# Amogus.net
KiCad netlist of a schematic drawn in EasyEDA
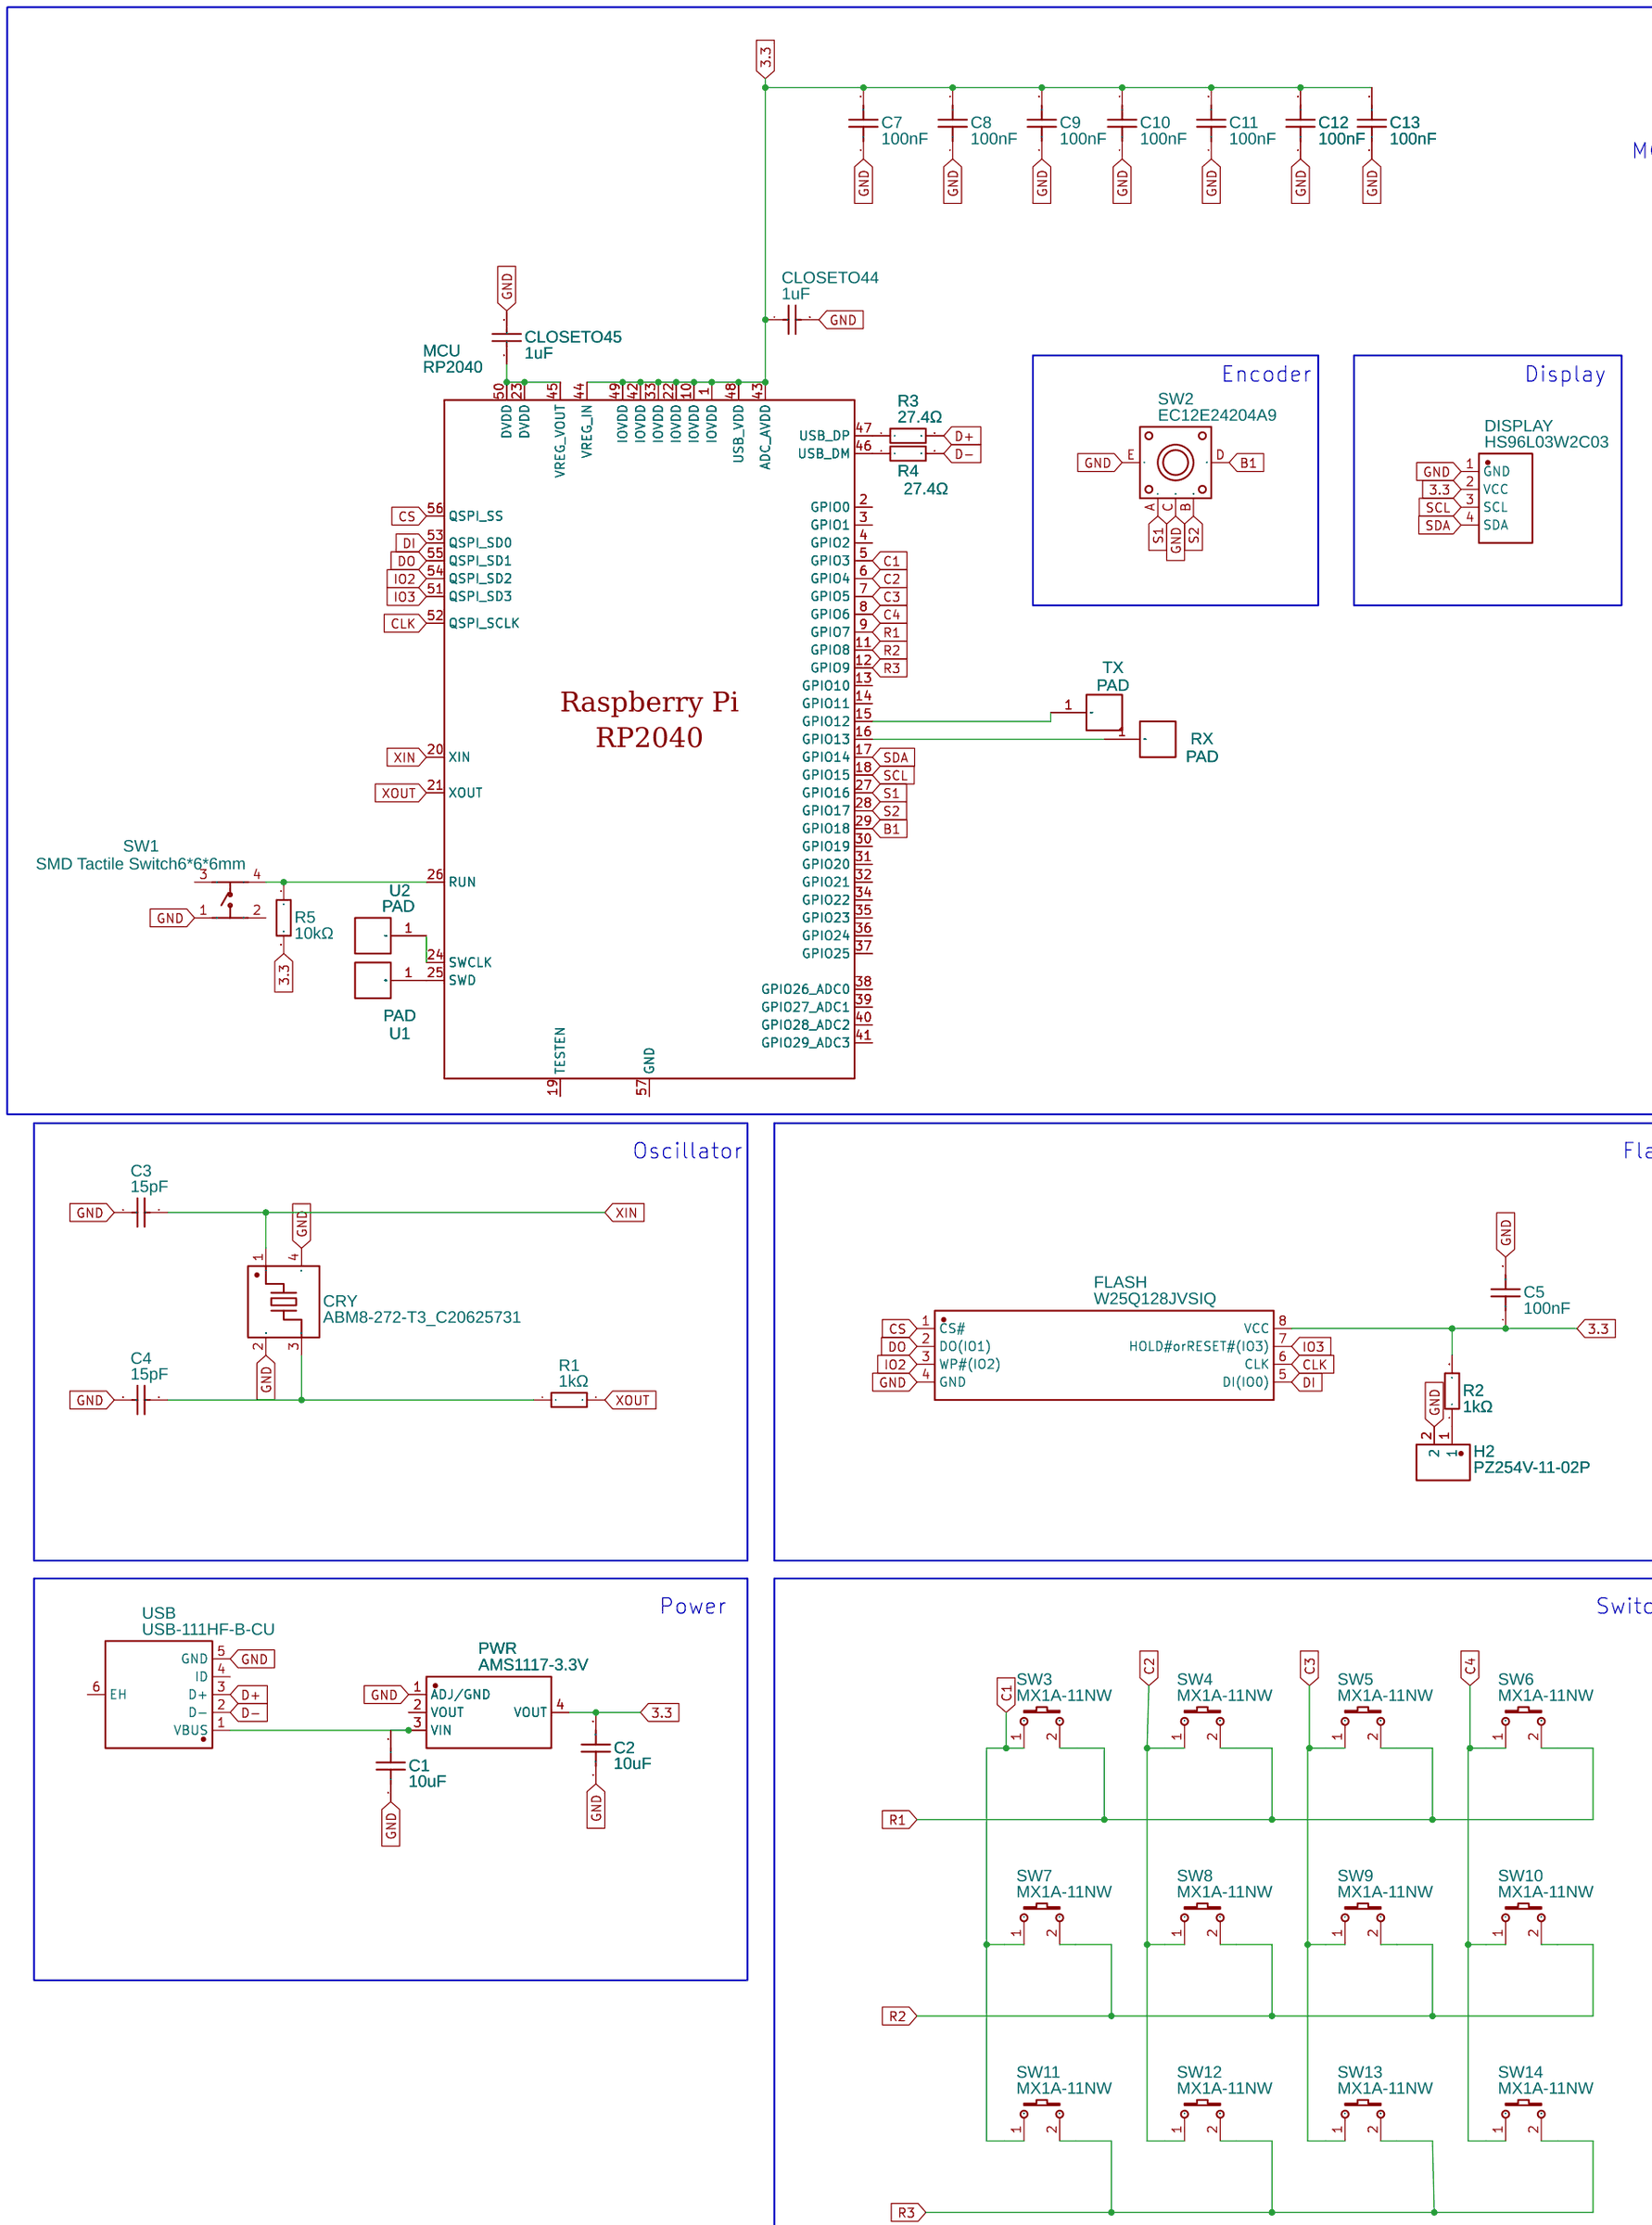
[diagram p0: schematic sheet]

(export (version "E")
  (design (tool "Eeschema 10.0.6"))
  (components
    (comp (ref "C1")
      (value "10uF")
      (fields
        (field (name "Manufacturer Part") "CL21A106KAYNNNE")
        (field (name "Manufacturer") "SAMSUNG(三星)")
      )
      (libsource (lib "") (part "CL21A106KAYNNNE"))
    )
    (comp (ref "C2")
      (value "10uF")
      (fields
        (field (name "Manufacturer Part") "CL21A106KAYNNNE")
        (field (name "Manufacturer") "SAMSUNG(三星)")
      )
      (libsource (lib "") (part "CL21A106KAYNNNE"))
    )
    (comp (ref "C3")
      (value "15pF")
      (fields (field (name "Manufacturer Part") "0805CG150J500NT") (field (name "Manufacturer") "FH(风华)"))
      (libsource (lib "") (part "0805CG150J500NT"))
    )
    (comp (ref "C4")
      (value "15pF")
      (fields (field (name "Manufacturer Part") "0805CG150J500NT") (field (name "Manufacturer") "FH(风华)"))
      (libsource (lib "") (part "0805CG150J500NT"))
    )
    (comp (ref "C5")
      (value "100nF")
      (fields
        (field (name "Manufacturer Part") "CC0603KRX7R9BB104")
        (field (name "Manufacturer") "YAGEO(国巨)")
      )
      (libsource (lib "") (part "CC0603KRX7R9BB104"))
    )
    (comp (ref "C7")
      (value "100nF")
      (fields
        (field (name "Manufacturer Part") "CC0603KRX7R9BB104")
        (field (name "Manufacturer") "YAGEO(国巨)")
      )
      (libsource (lib "") (part "CC0603KRX7R9BB104"))
    )
    (comp (ref "C8")
      (value "100nF")
      (fields
        (field (name "Manufacturer Part") "CC0603KRX7R9BB104")
        (field (name "Manufacturer") "YAGEO(国巨)")
      )
      (libsource (lib "") (part "CC0603KRX7R9BB104"))
    )
    (comp (ref "C9")
      (value "100nF")
      (fields
        (field (name "Manufacturer Part") "CC0603KRX7R9BB104")
        (field (name "Manufacturer") "YAGEO(国巨)")
      )
      (libsource (lib "") (part "CC0603KRX7R9BB104"))
    )
    (comp (ref "C10")
      (value "100nF")
      (fields
        (field (name "Manufacturer Part") "CC0603KRX7R9BB104")
        (field (name "Manufacturer") "YAGEO(国巨)")
      )
      (libsource (lib "") (part "CC0603KRX7R9BB104"))
    )
    (comp (ref "C11")
      (value "100nF")
      (fields
        (field (name "Manufacturer Part") "CC0603KRX7R9BB104")
        (field (name "Manufacturer") "YAGEO(国巨)")
      )
      (libsource (lib "") (part "CC0603KRX7R9BB104"))
    )
    (comp (ref "C12")
      (value "100nF")
      (fields
        (field (name "Manufacturer Part") "CC0603KRX7R9BB104")
        (field (name "Manufacturer") "YAGEO(国巨)")
      )
      (libsource (lib "") (part "CC0603KRX7R9BB104"))
    )
    (comp (ref "C13")
      (value "100nF")
      (fields
        (field (name "Manufacturer Part") "CC0603KRX7R9BB104")
        (field (name "Manufacturer") "YAGEO(国巨)")
      )
      (libsource (lib "") (part "CC0603KRX7R9BB104"))
    )
    (comp (ref "CLOSETO44")
      (value "1uF")
      (fields
        (field (name "Manufacturer Part") "GRM155R61E105KA12D")
        (field (name "Manufacturer") "muRata(村田)")
      )
      (libsource (lib "") (part "GRM155R61E105KA12D_1"))
    )
    (comp (ref "CLOSETO45")
      (value "1uF")
      (fields
        (field (name "Manufacturer Part") "GRM155R61E105KA12D")
        (field (name "Manufacturer") "muRata(村田)")
      )
      (libsource (lib "") (part "GRM155R61E105KA12D"))
    )
    (comp (ref "CRY")
      (value "ABM8-272-T3_C20625731")
      (fields (field (name "Manufacturer Part") "ABM8-272-T3") (field (name "Manufacturer") "ABRACON"))
      (libsource (lib "") (part "ABM8-272-T3_C20625731"))
    )
    (comp (ref "DISPLAY")
      (value "HS96L03W2C03")
      (fields (field (name "Manufacturer") "HS(汉昇)"))
      (libsource (lib "") (part "HS96L03W2C03"))
    )
    (comp (ref "FLASH")
      (value "W25Q128JVSIQ")
      (fields (field (name "Manufacturer") "WINBOND(华邦)"))
      (libsource (lib "") (part "W25Q128JVSIQ"))
    )
    (comp (ref "H2")
      (value "PZ254V-11-02P")
      (fields (field (name "Manufacturer") "XFCN(兴飞)"))
      (libsource (lib "") (part "PZ254V-11-02P"))
    )
    (comp (ref "MCU")
      (value "RP2040")
      (fields (field (name "Manufacturer") "Raspberry Pi(树莓派)"))
      (libsource (lib "") (part "RP2040"))
    )
    (comp (ref "PWR")
      (value "AMS1117-3.3V")
      (fields (field (name "Manufacturer") "WPMtek(维攀)"))
      (libsource (lib "") (part "AMS1117-3.3V"))
    )
    (comp (ref "R1")
      (value "1kΩ")
      (fields
        (field (name "Manufacturer Part") "0805W8F1001T5E")
        (field (name "Manufacturer") "UNI-ROYAL(厚声)")
      )
      (libsource (lib "") (part "0805W8F1001T5E_1"))
    )
    (comp (ref "R2")
      (value "1kΩ")
      (fields
        (field (name "Manufacturer Part") "0805W8F1001T5E")
        (field (name "Manufacturer") "UNI-ROYAL(厚声)")
      )
      (libsource (lib "") (part "0805W8F1001T5E"))
    )
    (comp (ref "R3")
      (value "27.4Ω")
      (fields (field (name "Manufacturer Part") "RS-03K27R4FT") (field (name "Manufacturer") "FH(风华)"))
      (libsource (lib "") (part "RS-03K27R4FT"))
    )
    (comp (ref "R4")
      (value "27.4Ω")
      (fields (field (name "Manufacturer Part") "RS-03K27R4FT") (field (name "Manufacturer") "FH(风华)"))
      (libsource (lib "") (part "RS-03K27R4FT"))
    )
    (comp (ref "R5")
      (value "10kΩ")
      (fields
        (field (name "Manufacturer Part") "0805W8F1002T5E")
        (field (name "Manufacturer") "UNI-ROYAL(厚声)")
      )
      (libsource (lib "") (part "0805W8F1002T5E"))
    )
    (comp (ref "RX") (value "PAD") (libsource (lib "") (part "PAD_1")))
    (comp (ref "SW1")
      (value "SMD Tactile Switch6*6*6mm")
      (fields (field (name "Manufacturer Part") "贴片轻触开关6*6*6mm"))
      (libsource (lib "") (part "SMD Tactile Switch6*6*6mm"))
    )
    (comp (ref "SW2")
      (value "EC12E24204A9")
      (fields (field (name "Manufacturer") "ALPSALPINE(阿尔卑斯阿尔派)"))
      (libsource (lib "") (part "EC12E24204A9"))
    )
    (comp (ref "SW3")
      (value "MX1A-11NW")
      (fields (field (name "Manufacturer") "CHERRY"))
      (libsource (lib "") (part "MX1A-11NW"))
    )
    (comp (ref "SW4")
      (value "MX1A-11NW")
      (fields (field (name "Manufacturer") "CHERRY"))
      (libsource (lib "") (part "MX1A-11NW"))
    )
    (comp (ref "SW5")
      (value "MX1A-11NW")
      (fields (field (name "Manufacturer") "CHERRY"))
      (libsource (lib "") (part "MX1A-11NW"))
    )
    (comp (ref "SW6")
      (value "MX1A-11NW")
      (fields (field (name "Manufacturer") "CHERRY"))
      (libsource (lib "") (part "MX1A-11NW"))
    )
    (comp (ref "SW7")
      (value "MX1A-11NW")
      (fields (field (name "Manufacturer") "CHERRY"))
      (libsource (lib "") (part "MX1A-11NW"))
    )
    (comp (ref "SW8")
      (value "MX1A-11NW")
      (fields (field (name "Manufacturer") "CHERRY"))
      (libsource (lib "") (part "MX1A-11NW"))
    )
    (comp (ref "SW9")
      (value "MX1A-11NW")
      (fields (field (name "Manufacturer") "CHERRY"))
      (libsource (lib "") (part "MX1A-11NW"))
    )
    (comp (ref "SW10")
      (value "MX1A-11NW")
      (fields (field (name "Manufacturer") "CHERRY"))
      (libsource (lib "") (part "MX1A-11NW"))
    )
    (comp (ref "SW11")
      (value "MX1A-11NW")
      (fields (field (name "Manufacturer") "CHERRY"))
      (libsource (lib "") (part "MX1A-11NW"))
    )
    (comp (ref "SW12")
      (value "MX1A-11NW")
      (fields (field (name "Manufacturer") "CHERRY"))
      (libsource (lib "") (part "MX1A-11NW"))
    )
    (comp (ref "SW13")
      (value "MX1A-11NW")
      (fields (field (name "Manufacturer") "CHERRY"))
      (libsource (lib "") (part "MX1A-11NW"))
    )
    (comp (ref "SW14")
      (value "MX1A-11NW")
      (fields (field (name "Manufacturer") "CHERRY"))
      (libsource (lib "") (part "MX1A-11NW"))
    )
    (comp (ref "TX") (value "PAD") (libsource (lib "") (part "PAD_2")))
    (comp (ref "U1") (value "PAD") (libsource (lib "") (part "PAD")))
    (comp (ref "U2") (value "PAD") (libsource (lib "") (part "PAD")))
    (comp (ref "USB")
      (value "USB-111HF-B-CU")
      (fields (field (name "Manufacturer") "HOOYA(皓宇电子)"))
      (libsource (lib "") (part "USB-111HF-B-CU"))
    )
  )
  (nets
    (net (code "1") (name "3.3") (class "Default")
      (node (ref "C10") (pin "2") (pinfunction "2_2") (pintype "unspecified"))
      (node (ref "C11") (pin "2") (pinfunction "2_2") (pintype "unspecified"))
      (node (ref "C12") (pin "2") (pinfunction "2_2") (pintype "unspecified"))
      (node (ref "C13") (pin "2") (pinfunction "2_2") (pintype "unspecified"))
      (node (ref "C2") (pin "2") (pinfunction "2_2") (pintype "unspecified"))
      (node (ref "C5") (pin "1") (pinfunction "1_1") (pintype "unspecified"))
      (node (ref "C7") (pin "2") (pinfunction "2_2") (pintype "unspecified"))
      (node (ref "C8") (pin "2") (pinfunction "2_2") (pintype "unspecified"))
      (node (ref "C9") (pin "2") (pinfunction "2_2") (pintype "unspecified"))
      (node (ref "CLOSETO44") (pin "1") (pinfunction "1_1") (pintype "input"))
      (node (ref "DISPLAY") (pin "2") (pinfunction "VCC_2") (pintype "unspecified"))
      (node (ref "FLASH") (pin "8") (pinfunction "VCC_8") (pintype "unspecified"))
      (node (ref "MCU") (pin "1") (pinfunction "IOVDD_1") (pintype "bidirectional"))
      (node (ref "MCU") (pin "10") (pinfunction "IOVDD_10") (pintype "bidirectional"))
      (node (ref "MCU") (pin "22") (pinfunction "IOVDD_22") (pintype "bidirectional"))
      (node (ref "MCU") (pin "33") (pinfunction "IOVDD_33") (pintype "bidirectional"))
      (node (ref "MCU") (pin "42") (pinfunction "IOVDD_42") (pintype "bidirectional"))
      (node (ref "MCU") (pin "43") (pinfunction "ADC_AVDD_43") (pintype "bidirectional"))
      (node (ref "MCU") (pin "44") (pinfunction "VREG_IN_44") (pintype "bidirectional"))
      (node (ref "MCU") (pin "48") (pinfunction "USB_VDD_48") (pintype "bidirectional"))
      (node (ref "MCU") (pin "49") (pinfunction "IOVDD_49") (pintype "bidirectional"))
      (node (ref "PWR") (pin "4") (pinfunction "VOUT_4") (pintype "unspecified"))
      (node (ref "R2") (pin "2") (pinfunction "2_2") (pintype "input"))
      (node (ref "R5") (pin "2") (pinfunction "2_2") (pintype "input"))
    )
    (net (code "2") (name "B1") (class "Default")
      (node (ref "MCU") (pin "29") (pinfunction "GPIO18_29") (pintype "bidirectional"))
      (node (ref "SW2") (pin "D") (pinfunction "D_D") (pintype "unspecified"))
    )
    (net (code "3") (name "C1") (class "Default")
      (node (ref "MCU") (pin "5") (pinfunction "GPIO3_5") (pintype "bidirectional"))
      (node (ref "SW11") (pin "1") (pinfunction "1_1") (pintype "unspecified"))
      (node (ref "SW3") (pin "1") (pinfunction "1_1") (pintype "unspecified"))
      (node (ref "SW7") (pin "1") (pinfunction "1_1") (pintype "unspecified"))
    )
    (net (code "4") (name "C2") (class "Default")
      (node (ref "MCU") (pin "6") (pinfunction "GPIO4_6") (pintype "bidirectional"))
      (node (ref "SW12") (pin "1") (pinfunction "1_1") (pintype "unspecified"))
      (node (ref "SW4") (pin "1") (pinfunction "1_1") (pintype "unspecified"))
      (node (ref "SW8") (pin "1") (pinfunction "1_1") (pintype "unspecified"))
    )
    (net (code "5") (name "C3") (class "Default")
      (node (ref "MCU") (pin "7") (pinfunction "GPIO5_7") (pintype "bidirectional"))
      (node (ref "SW13") (pin "1") (pinfunction "1_1") (pintype "unspecified"))
      (node (ref "SW5") (pin "1") (pinfunction "1_1") (pintype "unspecified"))
      (node (ref "SW9") (pin "1") (pinfunction "1_1") (pintype "unspecified"))
    )
    (net (code "6") (name "C4") (class "Default")
      (node (ref "MCU") (pin "8") (pinfunction "GPIO6_8") (pintype "bidirectional"))
      (node (ref "SW10") (pin "1") (pinfunction "1_1") (pintype "unspecified"))
      (node (ref "SW14") (pin "1") (pinfunction "1_1") (pintype "unspecified"))
      (node (ref "SW6") (pin "1") (pinfunction "1_1") (pintype "unspecified"))
    )
    (net (code "7") (name "CLK") (class "Default")
      (node (ref "FLASH") (pin "6") (pinfunction "CLK_6") (pintype "unspecified"))
      (node (ref "MCU") (pin "52") (pinfunction "QSPI_SCLK_52") (pintype "output"))
    )
    (net (code "8") (name "CS") (class "Default")
      (node (ref "FLASH") (pin "1") (pinfunction "CS#_1") (pintype "unspecified"))
      (node (ref "MCU") (pin "56") (pinfunction "QSPI_SS_56") (pintype "bidirectional"))
    )
    (net (code "9") (name "D+") (class "Default")
      (node (ref "R3") (pin "2") (pinfunction "2_2") (pintype "unspecified"))
      (node (ref "USB") (pin "3") (pinfunction "D+_3") (pintype "unspecified"))
    )
    (net (code "10") (name "D-") (class "Default")
      (node (ref "R4") (pin "2") (pinfunction "2_2") (pintype "unspecified"))
      (node (ref "USB") (pin "2") (pinfunction "D-_2") (pintype "unspecified"))
    )
    (net (code "11") (name "DI") (class "Default")
      (node (ref "FLASH") (pin "5") (pinfunction "DI(IO0)_5") (pintype "unspecified"))
      (node (ref "MCU") (pin "53") (pinfunction "QSPI_SD0_53") (pintype "bidirectional"))
    )
    (net (code "12") (name "DO") (class "Default")
      (node (ref "FLASH") (pin "2") (pinfunction "DO(IO1)_2") (pintype "unspecified"))
      (node (ref "MCU") (pin "55") (pinfunction "QSPI_SD1_55") (pintype "bidirectional"))
    )
    (net (code "13") (name "GND") (class "Default")
      (node (ref "C1") (pin "1") (pinfunction "1_1") (pintype "unspecified"))
      (node (ref "C10") (pin "1") (pinfunction "1_1") (pintype "unspecified"))
      (node (ref "C11") (pin "1") (pinfunction "1_1") (pintype "unspecified"))
      (node (ref "C12") (pin "1") (pinfunction "1_1") (pintype "unspecified"))
      (node (ref "C13") (pin "1") (pinfunction "1_1") (pintype "unspecified"))
      (node (ref "C2") (pin "1") (pinfunction "1_1") (pintype "unspecified"))
      (node (ref "C3") (pin "2") (pinfunction "2_2") (pintype "input"))
      (node (ref "C4") (pin "2") (pinfunction "2_2") (pintype "input"))
      (node (ref "C5") (pin "2") (pinfunction "2_2") (pintype "unspecified"))
      (node (ref "C7") (pin "1") (pinfunction "1_1") (pintype "unspecified"))
      (node (ref "C8") (pin "1") (pinfunction "1_1") (pintype "unspecified"))
      (node (ref "C9") (pin "1") (pinfunction "1_1") (pintype "unspecified"))
      (node (ref "CLOSETO44") (pin "2") (pinfunction "2_2") (pintype "input"))
      (node (ref "CLOSETO45") (pin "1") (pinfunction "1_1") (pintype "input"))
      (node (ref "CRY") (pin "2") (pinfunction "GND_2") (pintype "input"))
      (node (ref "CRY") (pin "4") (pinfunction "GND_4") (pintype "input"))
      (node (ref "DISPLAY") (pin "1") (pinfunction "GND_1") (pintype "unspecified"))
      (node (ref "FLASH") (pin "4") (pinfunction "GND_4") (pintype "unspecified"))
      (node (ref "H2") (pin "2") (pinfunction "2_2") (pintype "unspecified"))
      (node (ref "PWR") (pin "1") (pinfunction "ADJ/GND_1") (pintype "unspecified"))
      (node (ref "SW1") (pin "1") (pinfunction "1_1") (pintype "unspecified"))
      (node (ref "SW2") (pin "C") (pinfunction "C_C") (pintype "unspecified"))
      (node (ref "SW2") (pin "E") (pinfunction "E_E") (pintype "unspecified"))
      (node (ref "USB") (pin "5") (pinfunction "GND_5") (pintype "unspecified"))
    )
    (net (code "14") (name "IO2") (class "Default")
      (node (ref "FLASH") (pin "3") (pinfunction "WP#(IO2)_3") (pintype "unspecified"))
      (node (ref "MCU") (pin "54") (pinfunction "QSPI_SD2_54") (pintype "bidirectional"))
    )
    (net (code "15") (name "IO3") (class "Default")
      (node (ref "FLASH") (pin "7") (pinfunction "HOLD#orRESET#(IO3)_7") (pintype "unspecified"))
      (node (ref "MCU") (pin "51") (pinfunction "QSPI_SD3_51") (pintype "bidirectional"))
    )
    (net (code "16") (name "Net-(C4-Pad1)") (class "Default")
      (node (ref "C4") (pin "1") (pinfunction "1_1") (pintype "input"))
      (node (ref "CRY") (pin "3") (pinfunction "3_3") (pintype "input"))
      (node (ref "R1") (pin "1") (pinfunction "1_1") (pintype "input"))
    )
    (net (code "17") (name "Net-(H2-Pad1)") (class "Default")
      (node (ref "H2") (pin "1") (pinfunction "1_1") (pintype "unspecified"))
      (node (ref "R2") (pin "1") (pinfunction "1_1") (pintype "input"))
    )
    (net (code "18") (name "Net-(MCU-GPIO12)") (class "Default")
      (node (ref "MCU") (pin "15") (pinfunction "GPIO12_15") (pintype "bidirectional"))
      (node (ref "TX") (pin "1") (pinfunction "PADPAD123_1") (pintype "unspecified"))
    )
    (net (code "19") (name "Net-(MCU-GPIO13)") (class "Default")
      (node (ref "MCU") (pin "16") (pinfunction "GPIO13_16") (pintype "bidirectional"))
      (node (ref "RX") (pin "1") (pinfunction "PADPAD123_1") (pintype "unspecified"))
    )
    (net (code "20") (name "Net-(MCU-RUN)") (class "Default")
      (node (ref "MCU") (pin "26") (pinfunction "RUN_26") (pintype "input"))
      (node (ref "R5") (pin "1") (pinfunction "1_1") (pintype "input"))
      (node (ref "SW1") (pin "4") (pinfunction "4_4") (pintype "unspecified"))
    )
    (net (code "21") (name "Net-(MCU-SWCLK)") (class "Default")
      (node (ref "MCU") (pin "24") (pinfunction "SWCLK_24") (pintype "output"))
      (node (ref "U2") (pin "1") (pinfunction "PADPAD123_1") (pintype "unspecified"))
    )
    (net (code "22") (name "Net-(MCU-SWD)") (class "Default")
      (node (ref "MCU") (pin "25") (pinfunction "SWD_25") (pintype "bidirectional"))
      (node (ref "U1") (pin "1") (pinfunction "PADPAD123_1") (pintype "unspecified"))
    )
    (net (code "23") (name "Net-(MCU-USB_DM)") (class "Default")
      (node (ref "MCU") (pin "46") (pinfunction "USB_DM_46") (pintype "bidirectional"))
      (node (ref "R4") (pin "1") (pinfunction "1_1") (pintype "unspecified"))
    )
    (net (code "24") (name "Net-(MCU-USB_DP)") (class "Default")
      (node (ref "MCU") (pin "47") (pinfunction "USB_DP_47") (pintype "bidirectional"))
      (node (ref "R3") (pin "1") (pinfunction "1_1") (pintype "unspecified"))
    )
    (net (code "25") (name "Net-(MCU-VREG_VOUT)") (class "Default")
      (node (ref "CLOSETO45") (pin "2") (pinfunction "2_2") (pintype "input"))
      (node (ref "MCU") (pin "23") (pinfunction "DVDD_23") (pintype "bidirectional"))
      (node (ref "MCU") (pin "45") (pinfunction "VREG_VOUT_45") (pintype "bidirectional"))
      (node (ref "MCU") (pin "50") (pinfunction "DVDD_50") (pintype "bidirectional"))
    )
    (net (code "26") (name "Net-(PWR-VIN)") (class "Default")
      (node (ref "C1") (pin "2") (pinfunction "2_2") (pintype "unspecified"))
      (node (ref "PWR") (pin "3") (pinfunction "VIN_3") (pintype "unspecified"))
      (node (ref "USB") (pin "1") (pinfunction "VBUS_1") (pintype "unspecified"))
    )
    (net (code "27") (name "R1") (class "Default")
      (node (ref "MCU") (pin "9") (pinfunction "GPIO7_9") (pintype "bidirectional"))
      (node (ref "SW3") (pin "2") (pinfunction "2_2") (pintype "unspecified"))
      (node (ref "SW4") (pin "2") (pinfunction "2_2") (pintype "unspecified"))
      (node (ref "SW5") (pin "2") (pinfunction "2_2") (pintype "unspecified"))
      (node (ref "SW6") (pin "2") (pinfunction "2_2") (pintype "unspecified"))
    )
    (net (code "28") (name "R2") (class "Default")
      (node (ref "MCU") (pin "11") (pinfunction "GPIO8_11") (pintype "bidirectional"))
      (node (ref "SW10") (pin "2") (pinfunction "2_2") (pintype "unspecified"))
      (node (ref "SW7") (pin "2") (pinfunction "2_2") (pintype "unspecified"))
      (node (ref "SW8") (pin "2") (pinfunction "2_2") (pintype "unspecified"))
      (node (ref "SW9") (pin "2") (pinfunction "2_2") (pintype "unspecified"))
    )
    (net (code "29") (name "R3") (class "Default")
      (node (ref "MCU") (pin "12") (pinfunction "GPIO9_12") (pintype "bidirectional"))
      (node (ref "SW11") (pin "2") (pinfunction "2_2") (pintype "unspecified"))
      (node (ref "SW12") (pin "2") (pinfunction "2_2") (pintype "unspecified"))
      (node (ref "SW13") (pin "2") (pinfunction "2_2") (pintype "unspecified"))
      (node (ref "SW14") (pin "2") (pinfunction "2_2") (pintype "unspecified"))
    )
    (net (code "30") (name "S1") (class "Default")
      (node (ref "MCU") (pin "27") (pinfunction "GPIO16_27") (pintype "bidirectional"))
      (node (ref "SW2") (pin "A") (pinfunction "A_A") (pintype "unspecified"))
    )
    (net (code "31") (name "S2") (class "Default")
      (node (ref "MCU") (pin "28") (pinfunction "GPIO17_28") (pintype "bidirectional"))
      (node (ref "SW2") (pin "B") (pinfunction "B_B") (pintype "unspecified"))
    )
    (net (code "32") (name "SCL") (class "Default")
      (node (ref "DISPLAY") (pin "3") (pinfunction "SCL_3") (pintype "unspecified"))
      (node (ref "MCU") (pin "18") (pinfunction "GPIO15_18") (pintype "bidirectional"))
    )
    (net (code "33") (name "SDA") (class "Default")
      (node (ref "DISPLAY") (pin "4") (pinfunction "SDA_4") (pintype "unspecified"))
      (node (ref "MCU") (pin "17") (pinfunction "GPIO14_17") (pintype "bidirectional"))
    )
    (net (code "34") (name "XIN") (class "Default")
      (node (ref "C3") (pin "1") (pinfunction "1_1") (pintype "input"))
      (node (ref "CRY") (pin "1") (pinfunction "1_1") (pintype "input"))
      (node (ref "MCU") (pin "20") (pinfunction "XIN_20") (pintype "input"))
    )
    (net (code "35") (name "XOUT") (class "Default")
      (node (ref "MCU") (pin "21") (pinfunction "XOUT_21") (pintype "unspecified"))
      (node (ref "R1") (pin "2") (pinfunction "2_2") (pintype "input"))
    )
    (net (code "36") (name "unconnected-(MCU-GND-Pad57)") (class "Default")
      (node (ref "MCU") (pin "57") (pinfunction "GND_57") (pintype "bidirectional"))
    )
    (net (code "37") (name "unconnected-(MCU-GPIO0-Pad2)") (class "Default")
      (node (ref "MCU") (pin "2") (pinfunction "GPIO0_2") (pintype "bidirectional"))
    )
    (net (code "38") (name "unconnected-(MCU-GPIO1-Pad3)") (class "Default")
      (node (ref "MCU") (pin "3") (pinfunction "GPIO1_3") (pintype "bidirectional"))
    )
    (net (code "39") (name "unconnected-(MCU-GPIO2-Pad4)") (class "Default")
      (node (ref "MCU") (pin "4") (pinfunction "GPIO2_4") (pintype "bidirectional"))
    )
    (net (code "40") (name "unconnected-(MCU-GPIO10-Pad13)") (class "Default")
      (node (ref "MCU") (pin "13") (pinfunction "GPIO10_13") (pintype "bidirectional"))
    )
    (net (code "41") (name "unconnected-(MCU-GPIO11-Pad14)") (class "Default")
      (node (ref "MCU") (pin "14") (pinfunction "GPIO11_14") (pintype "bidirectional"))
    )
    (net (code "42") (name "unconnected-(MCU-GPIO19-Pad30)") (class "Default")
      (node (ref "MCU") (pin "30") (pinfunction "GPIO19_30") (pintype "bidirectional"))
    )
    (net (code "43") (name "unconnected-(MCU-GPIO20-Pad31)") (class "Default")
      (node (ref "MCU") (pin "31") (pinfunction "GPIO20_31") (pintype "bidirectional"))
    )
    (net (code "44") (name "unconnected-(MCU-GPIO21-Pad32)") (class "Default")
      (node (ref "MCU") (pin "32") (pinfunction "GPIO21_32") (pintype "bidirectional"))
    )
    (net (code "45") (name "unconnected-(MCU-GPIO22-Pad34)") (class "Default")
      (node (ref "MCU") (pin "34") (pinfunction "GPIO22_34") (pintype "bidirectional"))
    )
    (net (code "46") (name "unconnected-(MCU-GPIO23-Pad35)") (class "Default")
      (node (ref "MCU") (pin "35") (pinfunction "GPIO23_35") (pintype "bidirectional"))
    )
    (net (code "47") (name "unconnected-(MCU-GPIO24-Pad36)") (class "Default")
      (node (ref "MCU") (pin "36") (pinfunction "GPIO24_36") (pintype "bidirectional"))
    )
    (net (code "48") (name "unconnected-(MCU-GPIO25-Pad37)") (class "Default")
      (node (ref "MCU") (pin "37") (pinfunction "GPIO25_37") (pintype "bidirectional"))
    )
    (net (code "49") (name "unconnected-(MCU-GPIO26_ADC0-Pad38)") (class "Default")
      (node (ref "MCU") (pin "38") (pinfunction "GPIO26_ADC0_38") (pintype "bidirectional"))
    )
    (net (code "50") (name "unconnected-(MCU-GPIO27_ADC1-Pad39)") (class "Default")
      (node (ref "MCU") (pin "39") (pinfunction "GPIO27_ADC1_39") (pintype "bidirectional"))
    )
    (net (code "51") (name "unconnected-(MCU-GPIO28_ADC2-Pad40)") (class "Default")
      (node (ref "MCU") (pin "40") (pinfunction "GPIO28_ADC2_40") (pintype "bidirectional"))
    )
    (net (code "52") (name "unconnected-(MCU-GPIO29_ADC3-Pad41)") (class "Default")
      (node (ref "MCU") (pin "41") (pinfunction "GPIO29_ADC3_41") (pintype "bidirectional"))
    )
    (net (code "53") (name "unconnected-(MCU-TESTEN-Pad19)") (class "Default")
      (node (ref "MCU") (pin "19") (pinfunction "TESTEN_19") (pintype "unspecified"))
    )
    (net (code "54") (name "unconnected-(PWR-VOUT-Pad2)") (class "Default")
      (node (ref "PWR") (pin "2") (pinfunction "VOUT_2") (pintype "unspecified"))
    )
    (net (code "55") (name "unconnected-(SW1-Pad2)") (class "Default")
      (node (ref "SW1") (pin "2") (pinfunction "2_2") (pintype "unspecified"))
    )
    (net (code "56") (name "unconnected-(SW1-Pad3)") (class "Default")
      (node (ref "SW1") (pin "3") (pinfunction "3_3") (pintype "unspecified"))
    )
    (net (code "57") (name "unconnected-(USB-EH-Pad6)") (class "Default")
      (node (ref "USB") (pin "6") (pinfunction "EH_6") (pintype "unspecified"))
    )
    (net (code "58") (name "unconnected-(USB-ID-Pad4)") (class "Default")
      (node (ref "USB") (pin "4") (pinfunction "ID_4") (pintype "unspecified"))
    )
  )
)
